# Sheet1.net
KiCad netlist of a schematic drawn in Altium Designer
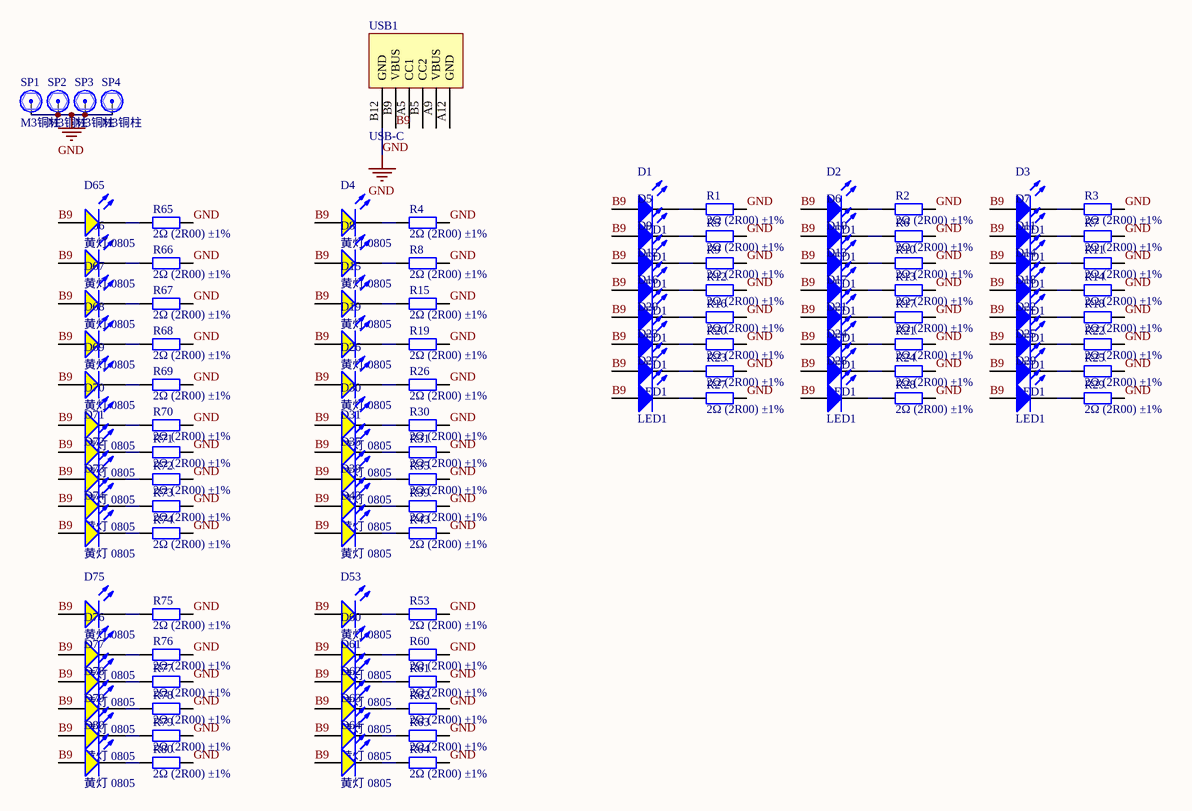
[diagram p0: Sheet1.SchDoc]

(export (version "E")
  (design (tool "Eeschema 10.0.6"))
  (components
    (comp (ref "D1")
      (value "LED1")
      (footprint "LED-1")
      (description "Typical RED GaAs LED")
      (fields (field (name "PUBLISHER") "Altium Limited"))
      (libsource (lib "Miscellaneous Devices") (part "LED1"))
    )
    (comp (ref "D2")
      (value "LED1")
      (footprint "LED-1")
      (description "Typical RED GaAs LED")
      (fields (field (name "PUBLISHER") "Altium Limited"))
      (libsource (lib "Miscellaneous Devices") (part "LED1"))
    )
    (comp (ref "D3")
      (value "LED1")
      (footprint "LED-1")
      (description "Typical RED GaAs LED")
      (fields (field (name "PUBLISHER") "Altium Limited"))
      (libsource (lib "Miscellaneous Devices") (part "LED1"))
    )
    (comp (ref "D4")
      (value "黄灯 0805")
      (footprint "0805_LED_S1")
      (description "发光二极管")
      (libsource (lib "Miscellaneous Devices LC") (part "0805 黄灯"))
    )
    (comp (ref "D5")
      (value "LED1")
      (footprint "LED-1")
      (description "Typical RED GaAs LED")
      (fields (field (name "PUBLISHER") "Altium Limited"))
      (libsource (lib "Miscellaneous Devices") (part "LED1"))
    )
    (comp (ref "D6")
      (value "LED1")
      (footprint "LED-1")
      (description "Typical RED GaAs LED")
      (fields (field (name "PUBLISHER") "Altium Limited"))
      (libsource (lib "Miscellaneous Devices") (part "LED1"))
    )
    (comp (ref "D7")
      (value "LED1")
      (footprint "LED-1")
      (description "Typical RED GaAs LED")
      (fields (field (name "PUBLISHER") "Altium Limited"))
      (libsource (lib "Miscellaneous Devices") (part "LED1"))
    )
    (comp (ref "D8")
      (value "黄灯 0805")
      (footprint "0805_LED_S1")
      (description "发光二极管")
      (libsource (lib "Miscellaneous Devices LC") (part "0805 黄灯"))
    )
    (comp (ref "D9")
      (value "LED1")
      (footprint "LED-1")
      (description "Typical RED GaAs LED")
      (fields (field (name "PUBLISHER") "Altium Limited"))
      (libsource (lib "Miscellaneous Devices") (part "LED1"))
    )
    (comp (ref "D10")
      (value "LED1")
      (footprint "LED-1")
      (description "Typical RED GaAs LED")
      (fields (field (name "PUBLISHER") "Altium Limited"))
      (libsource (lib "Miscellaneous Devices") (part "LED1"))
    )
    (comp (ref "D11")
      (value "LED1")
      (footprint "LED-1")
      (description "Typical RED GaAs LED")
      (fields (field (name "PUBLISHER") "Altium Limited"))
      (libsource (lib "Miscellaneous Devices") (part "LED1"))
    )
    (comp (ref "D12")
      (value "LED1")
      (footprint "LED-1")
      (description "Typical RED GaAs LED")
      (fields (field (name "PUBLISHER") "Altium Limited"))
      (libsource (lib "Miscellaneous Devices") (part "LED1"))
    )
    (comp (ref "D13")
      (value "LED1")
      (footprint "LED-1")
      (description "Typical RED GaAs LED")
      (fields (field (name "PUBLISHER") "Altium Limited"))
      (libsource (lib "Miscellaneous Devices") (part "LED1"))
    )
    (comp (ref "D14")
      (value "LED1")
      (footprint "LED-1")
      (description "Typical RED GaAs LED")
      (fields (field (name "PUBLISHER") "Altium Limited"))
      (libsource (lib "Miscellaneous Devices") (part "LED1"))
    )
    (comp (ref "D15")
      (value "黄灯 0805")
      (footprint "0805_LED_S1")
      (description "发光二极管")
      (libsource (lib "Miscellaneous Devices LC") (part "0805 黄灯"))
    )
    (comp (ref "D16")
      (value "LED1")
      (footprint "LED-1")
      (description "Typical RED GaAs LED")
      (fields (field (name "PUBLISHER") "Altium Limited"))
      (libsource (lib "Miscellaneous Devices") (part "LED1"))
    )
    (comp (ref "D17")
      (value "LED1")
      (footprint "LED-1")
      (description "Typical RED GaAs LED")
      (fields (field (name "PUBLISHER") "Altium Limited"))
      (libsource (lib "Miscellaneous Devices") (part "LED1"))
    )
    (comp (ref "D18")
      (value "LED1")
      (footprint "LED-1")
      (description "Typical RED GaAs LED")
      (fields (field (name "PUBLISHER") "Altium Limited"))
      (libsource (lib "Miscellaneous Devices") (part "LED1"))
    )
    (comp (ref "D19")
      (value "黄灯 0805")
      (footprint "0805_LED_S1")
      (description "发光二极管")
      (libsource (lib "Miscellaneous Devices LC") (part "0805 黄灯"))
    )
    (comp (ref "D20")
      (value "LED1")
      (footprint "LED-1")
      (description "Typical RED GaAs LED")
      (fields (field (name "PUBLISHER") "Altium Limited"))
      (libsource (lib "Miscellaneous Devices") (part "LED1"))
    )
    (comp (ref "D21")
      (value "LED1")
      (footprint "LED-1")
      (description "Typical RED GaAs LED")
      (fields (field (name "PUBLISHER") "Altium Limited"))
      (libsource (lib "Miscellaneous Devices") (part "LED1"))
    )
    (comp (ref "D22")
      (value "LED1")
      (footprint "LED-1")
      (description "Typical RED GaAs LED")
      (fields (field (name "PUBLISHER") "Altium Limited"))
      (libsource (lib "Miscellaneous Devices") (part "LED1"))
    )
    (comp (ref "D23")
      (value "LED1")
      (footprint "LED-1")
      (description "Typical RED GaAs LED")
      (fields (field (name "PUBLISHER") "Altium Limited"))
      (libsource (lib "Miscellaneous Devices") (part "LED1"))
    )
    (comp (ref "D24")
      (value "LED1")
      (footprint "LED-1")
      (description "Typical RED GaAs LED")
      (fields (field (name "PUBLISHER") "Altium Limited"))
      (libsource (lib "Miscellaneous Devices") (part "LED1"))
    )
    (comp (ref "D25")
      (value "LED1")
      (footprint "LED-1")
      (description "Typical RED GaAs LED")
      (fields (field (name "PUBLISHER") "Altium Limited"))
      (libsource (lib "Miscellaneous Devices") (part "LED1"))
    )
    (comp (ref "D26")
      (value "黄灯 0805")
      (footprint "0805_LED_S1")
      (description "发光二极管")
      (libsource (lib "Miscellaneous Devices LC") (part "0805 黄灯"))
    )
    (comp (ref "D27")
      (value "LED1")
      (footprint "LED-1")
      (description "Typical RED GaAs LED")
      (fields (field (name "PUBLISHER") "Altium Limited"))
      (libsource (lib "Miscellaneous Devices") (part "LED1"))
    )
    (comp (ref "D28")
      (value "LED1")
      (footprint "LED-1")
      (description "Typical RED GaAs LED")
      (fields (field (name "PUBLISHER") "Altium Limited"))
      (libsource (lib "Miscellaneous Devices") (part "LED1"))
    )
    (comp (ref "D29")
      (value "LED1")
      (footprint "LED-1")
      (description "Typical RED GaAs LED")
      (fields (field (name "PUBLISHER") "Altium Limited"))
      (libsource (lib "Miscellaneous Devices") (part "LED1"))
    )
    (comp (ref "D30")
      (value "黄灯 0805")
      (footprint "0805_LED_S1")
      (description "发光二极管")
      (libsource (lib "Miscellaneous Devices LC") (part "0805 黄灯"))
    )
    (comp (ref "D31")
      (value "黄灯 0805")
      (footprint "0805_LED_S1")
      (description "发光二极管")
      (libsource (lib "Miscellaneous Devices LC") (part "0805 黄灯"))
    )
    (comp (ref "D35")
      (value "黄灯 0805")
      (footprint "0805_LED_S1")
      (description "发光二极管")
      (libsource (lib "Miscellaneous Devices LC") (part "0805 黄灯"))
    )
    (comp (ref "D39")
      (value "黄灯 0805")
      (footprint "0805_LED_S1")
      (description "发光二极管")
      (libsource (lib "Miscellaneous Devices LC") (part "0805 黄灯"))
    )
    (comp (ref "D43")
      (value "黄灯 0805")
      (footprint "0805_LED_S1")
      (description "发光二极管")
      (libsource (lib "Miscellaneous Devices LC") (part "0805 黄灯"))
    )
    (comp (ref "D53")
      (value "黄灯 0805")
      (footprint "0805_LED_S1")
      (description "发光二极管")
      (libsource (lib "Miscellaneous Devices LC") (part "0805 黄灯"))
    )
    (comp (ref "D60")
      (value "黄灯 0805")
      (footprint "0805_LED_S1")
      (description "发光二极管")
      (libsource (lib "Miscellaneous Devices LC") (part "0805 黄灯"))
    )
    (comp (ref "D61")
      (value "黄灯 0805")
      (footprint "0805_LED_S1")
      (description "发光二极管")
      (libsource (lib "Miscellaneous Devices LC") (part "0805 黄灯"))
    )
    (comp (ref "D62")
      (value "黄灯 0805")
      (footprint "0805_LED_S1")
      (description "发光二极管")
      (libsource (lib "Miscellaneous Devices LC") (part "0805 黄灯"))
    )
    (comp (ref "D63")
      (value "黄灯 0805")
      (footprint "0805_LED_S1")
      (description "发光二极管")
      (libsource (lib "Miscellaneous Devices LC") (part "0805 黄灯"))
    )
    (comp (ref "D64")
      (value "黄灯 0805")
      (footprint "0805_LED_S1")
      (description "发光二极管")
      (libsource (lib "Miscellaneous Devices LC") (part "0805 黄灯"))
    )
    (comp (ref "D65")
      (value "黄灯 0805")
      (footprint "0805_LED_S1")
      (description "发光二极管")
      (libsource (lib "Miscellaneous Devices LC") (part "0805 黄灯"))
    )
    (comp (ref "D66")
      (value "黄灯 0805")
      (footprint "0805_LED_S1")
      (description "发光二极管")
      (libsource (lib "Miscellaneous Devices LC") (part "0805 黄灯"))
    )
    (comp (ref "D67")
      (value "黄灯 0805")
      (footprint "0805_LED_S1")
      (description "发光二极管")
      (libsource (lib "Miscellaneous Devices LC") (part "0805 黄灯"))
    )
    (comp (ref "D68")
      (value "黄灯 0805")
      (footprint "0805_LED_S1")
      (description "发光二极管")
      (libsource (lib "Miscellaneous Devices LC") (part "0805 黄灯"))
    )
    (comp (ref "D69")
      (value "黄灯 0805")
      (footprint "0805_LED_S1")
      (description "发光二极管")
      (libsource (lib "Miscellaneous Devices LC") (part "0805 黄灯"))
    )
    (comp (ref "D70")
      (value "黄灯 0805")
      (footprint "0805_LED_S1")
      (description "发光二极管")
      (libsource (lib "Miscellaneous Devices LC") (part "0805 黄灯"))
    )
    (comp (ref "D71")
      (value "黄灯 0805")
      (footprint "0805_LED_S1")
      (description "发光二极管")
      (libsource (lib "Miscellaneous Devices LC") (part "0805 黄灯"))
    )
    (comp (ref "D72")
      (value "黄灯 0805")
      (footprint "0805_LED_S1")
      (description "发光二极管")
      (libsource (lib "Miscellaneous Devices LC") (part "0805 黄灯"))
    )
    (comp (ref "D73")
      (value "黄灯 0805")
      (footprint "0805_LED_S1")
      (description "发光二极管")
      (libsource (lib "Miscellaneous Devices LC") (part "0805 黄灯"))
    )
    (comp (ref "D74")
      (value "黄灯 0805")
      (footprint "0805_LED_S1")
      (description "发光二极管")
      (libsource (lib "Miscellaneous Devices LC") (part "0805 黄灯"))
    )
    (comp (ref "D75")
      (value "黄灯 0805")
      (footprint "0805_LED_S1")
      (description "发光二极管")
      (libsource (lib "Miscellaneous Devices LC") (part "0805 黄灯"))
    )
    (comp (ref "D76")
      (value "黄灯 0805")
      (footprint "0805_LED_S1")
      (description "发光二极管")
      (libsource (lib "Miscellaneous Devices LC") (part "0805 黄灯"))
    )
    (comp (ref "D77")
      (value "黄灯 0805")
      (footprint "0805_LED_S1")
      (description "发光二极管")
      (libsource (lib "Miscellaneous Devices LC") (part "0805 黄灯"))
    )
    (comp (ref "D78")
      (value "黄灯 0805")
      (footprint "0805_LED_S1")
      (description "发光二极管")
      (libsource (lib "Miscellaneous Devices LC") (part "0805 黄灯"))
    )
    (comp (ref "D79")
      (value "黄灯 0805")
      (footprint "0805_LED_S1")
      (description "发光二极管")
      (libsource (lib "Miscellaneous Devices LC") (part "0805 黄灯"))
    )
    (comp (ref "D80")
      (value "黄灯 0805")
      (footprint "0805_LED_S1")
      (description "发光二极管")
      (libsource (lib "Miscellaneous Devices LC") (part "0805 黄灯"))
    )
    (comp (ref "R1")
      (value "2Ω (2R00) ±1%")
      (footprint "0805_R")
      (description "贴片电阻")
      (libsource (lib "Miscellaneous Devices LC") (part "0805 2Ω (2R00) 1%"))
    )
    (comp (ref "R2")
      (value "2Ω (2R00) ±1%")
      (footprint "0805_R")
      (description "贴片电阻")
      (libsource (lib "Miscellaneous Devices LC") (part "0805 2Ω (2R00) 1%"))
    )
    (comp (ref "R3")
      (value "2Ω (2R00) ±1%")
      (footprint "0805_R")
      (description "贴片电阻")
      (libsource (lib "Miscellaneous Devices LC") (part "0805 2Ω (2R00) 1%"))
    )
    (comp (ref "R4")
      (value "2Ω (2R00) ±1%")
      (footprint "0805_R")
      (description "贴片电阻")
      (libsource (lib "Miscellaneous Devices LC") (part "0805 2Ω (2R00) 1%"))
    )
    (comp (ref "R5")
      (value "2Ω (2R00) ±1%")
      (footprint "0805_R")
      (description "贴片电阻")
      (libsource (lib "Miscellaneous Devices LC") (part "0805 2Ω (2R00) 1%"))
    )
    (comp (ref "R6")
      (value "2Ω (2R00) ±1%")
      (footprint "0805_R")
      (description "贴片电阻")
      (libsource (lib "Miscellaneous Devices LC") (part "0805 2Ω (2R00) 1%"))
    )
    (comp (ref "R7")
      (value "2Ω (2R00) ±1%")
      (footprint "0805_R")
      (description "贴片电阻")
      (libsource (lib "Miscellaneous Devices LC") (part "0805 2Ω (2R00) 1%"))
    )
    (comp (ref "R8")
      (value "2Ω (2R00) ±1%")
      (footprint "0805_R")
      (description "贴片电阻")
      (libsource (lib "Miscellaneous Devices LC") (part "0805 2Ω (2R00) 1%"))
    )
    (comp (ref "R9")
      (value "2Ω (2R00) ±1%")
      (footprint "0805_R")
      (description "贴片电阻")
      (libsource (lib "Miscellaneous Devices LC") (part "0805 2Ω (2R00) 1%"))
    )
    (comp (ref "R10")
      (value "2Ω (2R00) ±1%")
      (footprint "0805_R")
      (description "贴片电阻")
      (libsource (lib "Miscellaneous Devices LC") (part "0805 2Ω (2R00) 1%"))
    )
    (comp (ref "R11")
      (value "2Ω (2R00) ±1%")
      (footprint "0805_R")
      (description "贴片电阻")
      (libsource (lib "Miscellaneous Devices LC") (part "0805 2Ω (2R00) 1%"))
    )
    (comp (ref "R12")
      (value "2Ω (2R00) ±1%")
      (footprint "0805_R")
      (description "贴片电阻")
      (libsource (lib "Miscellaneous Devices LC") (part "0805 2Ω (2R00) 1%"))
    )
    (comp (ref "R13")
      (value "2Ω (2R00) ±1%")
      (footprint "0805_R")
      (description "贴片电阻")
      (libsource (lib "Miscellaneous Devices LC") (part "0805 2Ω (2R00) 1%"))
    )
    (comp (ref "R14")
      (value "2Ω (2R00) ±1%")
      (footprint "0805_R")
      (description "贴片电阻")
      (libsource (lib "Miscellaneous Devices LC") (part "0805 2Ω (2R00) 1%"))
    )
    (comp (ref "R15")
      (value "2Ω (2R00) ±1%")
      (footprint "0805_R")
      (description "贴片电阻")
      (libsource (lib "Miscellaneous Devices LC") (part "0805 2Ω (2R00) 1%"))
    )
    (comp (ref "R16")
      (value "2Ω (2R00) ±1%")
      (footprint "0805_R")
      (description "贴片电阻")
      (libsource (lib "Miscellaneous Devices LC") (part "0805 2Ω (2R00) 1%"))
    )
    (comp (ref "R17")
      (value "2Ω (2R00) ±1%")
      (footprint "0805_R")
      (description "贴片电阻")
      (libsource (lib "Miscellaneous Devices LC") (part "0805 2Ω (2R00) 1%"))
    )
    (comp (ref "R18")
      (value "2Ω (2R00) ±1%")
      (footprint "0805_R")
      (description "贴片电阻")
      (libsource (lib "Miscellaneous Devices LC") (part "0805 2Ω (2R00) 1%"))
    )
    (comp (ref "R19")
      (value "2Ω (2R00) ±1%")
      (footprint "0805_R")
      (description "贴片电阻")
      (libsource (lib "Miscellaneous Devices LC") (part "0805 2Ω (2R00) 1%"))
    )
    (comp (ref "R20")
      (value "2Ω (2R00) ±1%")
      (footprint "0805_R")
      (description "贴片电阻")
      (libsource (lib "Miscellaneous Devices LC") (part "0805 2Ω (2R00) 1%"))
    )
    (comp (ref "R21")
      (value "2Ω (2R00) ±1%")
      (footprint "0805_R")
      (description "贴片电阻")
      (libsource (lib "Miscellaneous Devices LC") (part "0805 2Ω (2R00) 1%"))
    )
    (comp (ref "R22")
      (value "2Ω (2R00) ±1%")
      (footprint "0805_R")
      (description "贴片电阻")
      (libsource (lib "Miscellaneous Devices LC") (part "0805 2Ω (2R00) 1%"))
    )
    (comp (ref "R23")
      (value "2Ω (2R00) ±1%")
      (footprint "0805_R")
      (description "贴片电阻")
      (libsource (lib "Miscellaneous Devices LC") (part "0805 2Ω (2R00) 1%"))
    )
    (comp (ref "R24")
      (value "2Ω (2R00) ±1%")
      (footprint "0805_R")
      (description "贴片电阻")
      (libsource (lib "Miscellaneous Devices LC") (part "0805 2Ω (2R00) 1%"))
    )
    (comp (ref "R25")
      (value "2Ω (2R00) ±1%")
      (footprint "0805_R")
      (description "贴片电阻")
      (libsource (lib "Miscellaneous Devices LC") (part "0805 2Ω (2R00) 1%"))
    )
    (comp (ref "R26")
      (value "2Ω (2R00) ±1%")
      (footprint "0805_R")
      (description "贴片电阻")
      (libsource (lib "Miscellaneous Devices LC") (part "0805 2Ω (2R00) 1%"))
    )
    (comp (ref "R27")
      (value "2Ω (2R00) ±1%")
      (footprint "0805_R")
      (description "贴片电阻")
      (libsource (lib "Miscellaneous Devices LC") (part "0805 2Ω (2R00) 1%"))
    )
    (comp (ref "R28")
      (value "2Ω (2R00) ±1%")
      (footprint "0805_R")
      (description "贴片电阻")
      (libsource (lib "Miscellaneous Devices LC") (part "0805 2Ω (2R00) 1%"))
    )
    (comp (ref "R29")
      (value "2Ω (2R00) ±1%")
      (footprint "0805_R")
      (description "贴片电阻")
      (libsource (lib "Miscellaneous Devices LC") (part "0805 2Ω (2R00) 1%"))
    )
    (comp (ref "R30")
      (value "2Ω (2R00) ±1%")
      (footprint "0805_R")
      (description "贴片电阻")
      (libsource (lib "Miscellaneous Devices LC") (part "0805 2Ω (2R00) 1%"))
    )
    (comp (ref "R31")
      (value "2Ω (2R00) ±1%")
      (footprint "0805_R")
      (description "贴片电阻")
      (libsource (lib "Miscellaneous Devices LC") (part "0805 2Ω (2R00) 1%"))
    )
    (comp (ref "R35")
      (value "2Ω (2R00) ±1%")
      (footprint "0805_R")
      (description "贴片电阻")
      (libsource (lib "Miscellaneous Devices LC") (part "0805 2Ω (2R00) 1%"))
    )
    (comp (ref "R39")
      (value "2Ω (2R00) ±1%")
      (footprint "0805_R")
      (description "贴片电阻")
      (libsource (lib "Miscellaneous Devices LC") (part "0805 2Ω (2R00) 1%"))
    )
    (comp (ref "R43")
      (value "2Ω (2R00) ±1%")
      (footprint "0805_R")
      (description "贴片电阻")
      (libsource (lib "Miscellaneous Devices LC") (part "0805 2Ω (2R00) 1%"))
    )
    (comp (ref "R53")
      (value "2Ω (2R00) ±1%")
      (footprint "0805_R")
      (description "贴片电阻")
      (libsource (lib "Miscellaneous Devices LC") (part "0805 2Ω (2R00) 1%"))
    )
    (comp (ref "R60")
      (value "2Ω (2R00) ±1%")
      (footprint "0805_R")
      (description "贴片电阻")
      (libsource (lib "Miscellaneous Devices LC") (part "0805 2Ω (2R00) 1%"))
    )
    (comp (ref "R61")
      (value "2Ω (2R00) ±1%")
      (footprint "0805_R")
      (description "贴片电阻")
      (libsource (lib "Miscellaneous Devices LC") (part "0805 2Ω (2R00) 1%"))
    )
    (comp (ref "R62")
      (value "2Ω (2R00) ±1%")
      (footprint "0805_R")
      (description "贴片电阻")
      (libsource (lib "Miscellaneous Devices LC") (part "0805 2Ω (2R00) 1%"))
    )
    (comp (ref "R63")
      (value "2Ω (2R00) ±1%")
      (footprint "0805_R")
      (description "贴片电阻")
      (libsource (lib "Miscellaneous Devices LC") (part "0805 2Ω (2R00) 1%"))
    )
    (comp (ref "R64")
      (value "2Ω (2R00) ±1%")
      (footprint "0805_R")
      (description "贴片电阻")
      (libsource (lib "Miscellaneous Devices LC") (part "0805 2Ω (2R00) 1%"))
    )
    (comp (ref "R65")
      (value "2Ω (2R00) ±1%")
      (footprint "0805_R")
      (description "贴片电阻")
      (libsource (lib "Miscellaneous Devices LC") (part "0805 2Ω (2R00) 1%"))
    )
    (comp (ref "R66")
      (value "2Ω (2R00) ±1%")
      (footprint "0805_R")
      (description "贴片电阻")
      (libsource (lib "Miscellaneous Devices LC") (part "0805 2Ω (2R00) 1%"))
    )
    (comp (ref "R67")
      (value "2Ω (2R00) ±1%")
      (footprint "0805_R")
      (description "贴片电阻")
      (libsource (lib "Miscellaneous Devices LC") (part "0805 2Ω (2R00) 1%"))
    )
    (comp (ref "R68")
      (value "2Ω (2R00) ±1%")
      (footprint "0805_R")
      (description "贴片电阻")
      (libsource (lib "Miscellaneous Devices LC") (part "0805 2Ω (2R00) 1%"))
    )
    (comp (ref "R69")
      (value "2Ω (2R00) ±1%")
      (footprint "0805_R")
      (description "贴片电阻")
      (libsource (lib "Miscellaneous Devices LC") (part "0805 2Ω (2R00) 1%"))
    )
    (comp (ref "R70")
      (value "2Ω (2R00) ±1%")
      (footprint "0805_R")
      (description "贴片电阻")
      (libsource (lib "Miscellaneous Devices LC") (part "0805 2Ω (2R00) 1%"))
    )
    (comp (ref "R71")
      (value "2Ω (2R00) ±1%")
      (footprint "0805_R")
      (description "贴片电阻")
      (libsource (lib "Miscellaneous Devices LC") (part "0805 2Ω (2R00) 1%"))
    )
    (comp (ref "R72")
      (value "2Ω (2R00) ±1%")
      (footprint "0805_R")
      (description "贴片电阻")
      (libsource (lib "Miscellaneous Devices LC") (part "0805 2Ω (2R00) 1%"))
    )
    (comp (ref "R73")
      (value "2Ω (2R00) ±1%")
      (footprint "0805_R")
      (description "贴片电阻")
      (libsource (lib "Miscellaneous Devices LC") (part "0805 2Ω (2R00) 1%"))
    )
    (comp (ref "R74")
      (value "2Ω (2R00) ±1%")
      (footprint "0805_R")
      (description "贴片电阻")
      (libsource (lib "Miscellaneous Devices LC") (part "0805 2Ω (2R00) 1%"))
    )
    (comp (ref "R75")
      (value "2Ω (2R00) ±1%")
      (footprint "0805_R")
      (description "贴片电阻")
      (libsource (lib "Miscellaneous Devices LC") (part "0805 2Ω (2R00) 1%"))
    )
    (comp (ref "R76")
      (value "2Ω (2R00) ±1%")
      (footprint "0805_R")
      (description "贴片电阻")
      (libsource (lib "Miscellaneous Devices LC") (part "0805 2Ω (2R00) 1%"))
    )
    (comp (ref "R77")
      (value "2Ω (2R00) ±1%")
      (footprint "0805_R")
      (description "贴片电阻")
      (libsource (lib "Miscellaneous Devices LC") (part "0805 2Ω (2R00) 1%"))
    )
    (comp (ref "R78")
      (value "2Ω (2R00) ±1%")
      (footprint "0805_R")
      (description "贴片电阻")
      (libsource (lib "Miscellaneous Devices LC") (part "0805 2Ω (2R00) 1%"))
    )
    (comp (ref "R79")
      (value "2Ω (2R00) ±1%")
      (footprint "0805_R")
      (description "贴片电阻")
      (libsource (lib "Miscellaneous Devices LC") (part "0805 2Ω (2R00) 1%"))
    )
    (comp (ref "R80")
      (value "2Ω (2R00) ±1%")
      (footprint "0805_R")
      (description "贴片电阻")
      (libsource (lib "Miscellaneous Devices LC") (part "0805 2Ω (2R00) 1%"))
    )
    (comp (ref "SP1")
      (value "M3铜柱")
      (footprint "M3x4_L")
      (description "铜柱")
      (libsource (lib "铜柱-测试点-电池座-蜂鸣器") (part "铜柱小焊盘"))
    )
    (comp (ref "SP2")
      (value "M3铜柱")
      (footprint "M3x4_L")
      (description "铜柱")
      (libsource (lib "铜柱-测试点-电池座-蜂鸣器") (part "铜柱小焊盘"))
    )
    (comp (ref "SP3")
      (value "M3铜柱")
      (footprint "M3x4_L")
      (description "铜柱")
      (libsource (lib "铜柱-测试点-电池座-蜂鸣器") (part "铜柱小焊盘"))
    )
    (comp (ref "SP4")
      (value "M3铜柱")
      (footprint "M3x4_L")
      (description "铜柱")
      (libsource (lib "铜柱-测试点-电池座-蜂鸣器") (part "铜柱小焊盘"))
    )
    (comp (ref "USB1")
      (value "USB-C")
      (footprint "USB-C/S_C")
      (description "USB-C_6P型母接口")
      (libsource (lib "接口") (part "USB-C_6P/S"))
    )
  )
  (nets
    (net (code "1") (name "/B9") (class "Default")
      (node (ref "D1") (pin "1") (pinfunction "A_1") (pintype "passive"))
      (node (ref "D10") (pin "1") (pinfunction "A_1") (pintype "passive"))
      (node (ref "D11") (pin "1") (pinfunction "A_1") (pintype "passive"))
      (node (ref "D12") (pin "1") (pinfunction "A_1") (pintype "passive"))
      (node (ref "D13") (pin "1") (pinfunction "A_1") (pintype "passive"))
      (node (ref "D14") (pin "1") (pinfunction "A_1") (pintype "passive"))
      (node (ref "D15") (pin "A") (pinfunction "A_A") (pintype "passive"))
      (node (ref "D16") (pin "1") (pinfunction "A_1") (pintype "passive"))
      (node (ref "D17") (pin "1") (pinfunction "A_1") (pintype "passive"))
      (node (ref "D18") (pin "1") (pinfunction "A_1") (pintype "passive"))
      (node (ref "D19") (pin "A") (pinfunction "A_A") (pintype "passive"))
      (node (ref "D2") (pin "1") (pinfunction "A_1") (pintype "passive"))
      (node (ref "D20") (pin "1") (pinfunction "A_1") (pintype "passive"))
      (node (ref "D21") (pin "1") (pinfunction "A_1") (pintype "passive"))
      (node (ref "D22") (pin "1") (pinfunction "A_1") (pintype "passive"))
      (node (ref "D23") (pin "1") (pinfunction "A_1") (pintype "passive"))
      (node (ref "D24") (pin "1") (pinfunction "A_1") (pintype "passive"))
      (node (ref "D25") (pin "1") (pinfunction "A_1") (pintype "passive"))
      (node (ref "D26") (pin "A") (pinfunction "A_A") (pintype "passive"))
      (node (ref "D27") (pin "1") (pinfunction "A_1") (pintype "passive"))
      (node (ref "D28") (pin "1") (pinfunction "A_1") (pintype "passive"))
      (node (ref "D29") (pin "1") (pinfunction "A_1") (pintype "passive"))
      (node (ref "D3") (pin "1") (pinfunction "A_1") (pintype "passive"))
      (node (ref "D30") (pin "A") (pinfunction "A_A") (pintype "passive"))
      (node (ref "D31") (pin "A") (pinfunction "A_A") (pintype "passive"))
      (node (ref "D35") (pin "A") (pinfunction "A_A") (pintype "passive"))
      (node (ref "D39") (pin "A") (pinfunction "A_A") (pintype "passive"))
      (node (ref "D4") (pin "A") (pinfunction "A_A") (pintype "passive"))
      (node (ref "D43") (pin "A") (pinfunction "A_A") (pintype "passive"))
      (node (ref "D5") (pin "1") (pinfunction "A_1") (pintype "passive"))
      (node (ref "D53") (pin "A") (pinfunction "A_A") (pintype "passive"))
      (node (ref "D6") (pin "1") (pinfunction "A_1") (pintype "passive"))
      (node (ref "D60") (pin "A") (pinfunction "A_A") (pintype "passive"))
      (node (ref "D61") (pin "A") (pinfunction "A_A") (pintype "passive"))
      (node (ref "D62") (pin "A") (pinfunction "A_A") (pintype "passive"))
      (node (ref "D63") (pin "A") (pinfunction "A_A") (pintype "passive"))
      (node (ref "D64") (pin "A") (pinfunction "A_A") (pintype "passive"))
      (node (ref "D65") (pin "A") (pinfunction "A_A") (pintype "passive"))
      (node (ref "D66") (pin "A") (pinfunction "A_A") (pintype "passive"))
      (node (ref "D67") (pin "A") (pinfunction "A_A") (pintype "passive"))
      (node (ref "D68") (pin "A") (pinfunction "A_A") (pintype "passive"))
      (node (ref "D69") (pin "A") (pinfunction "A_A") (pintype "passive"))
      (node (ref "D7") (pin "1") (pinfunction "A_1") (pintype "passive"))
      (node (ref "D70") (pin "A") (pinfunction "A_A") (pintype "passive"))
      (node (ref "D71") (pin "A") (pinfunction "A_A") (pintype "passive"))
      (node (ref "D72") (pin "A") (pinfunction "A_A") (pintype "passive"))
      (node (ref "D73") (pin "A") (pinfunction "A_A") (pintype "passive"))
      (node (ref "D74") (pin "A") (pinfunction "A_A") (pintype "passive"))
      (node (ref "D75") (pin "A") (pinfunction "A_A") (pintype "passive"))
      (node (ref "D76") (pin "A") (pinfunction "A_A") (pintype "passive"))
      (node (ref "D77") (pin "A") (pinfunction "A_A") (pintype "passive"))
      (node (ref "D78") (pin "A") (pinfunction "A_A") (pintype "passive"))
      (node (ref "D79") (pin "A") (pinfunction "A_A") (pintype "passive"))
      (node (ref "D8") (pin "A") (pinfunction "A_A") (pintype "passive"))
      (node (ref "D80") (pin "A") (pinfunction "A_A") (pintype "passive"))
      (node (ref "D9") (pin "1") (pinfunction "A_1") (pintype "passive"))
      (node (ref "USB1") (pin "B9") (pinfunction "VBUS_B9") (pintype "passive"))
    )
    (net (code "2") (name "GND") (class "Default")
      (node (ref "R1") (pin "2") (pinfunction "2_2") (pintype "passive"))
      (node (ref "R10") (pin "2") (pinfunction "2_2") (pintype "passive"))
      (node (ref "R11") (pin "2") (pinfunction "2_2") (pintype "passive"))
      (node (ref "R12") (pin "2") (pinfunction "2_2") (pintype "passive"))
      (node (ref "R13") (pin "2") (pinfunction "2_2") (pintype "passive"))
      (node (ref "R14") (pin "2") (pinfunction "2_2") (pintype "passive"))
      (node (ref "R15") (pin "2") (pinfunction "2_2") (pintype "passive"))
      (node (ref "R16") (pin "2") (pinfunction "2_2") (pintype "passive"))
      (node (ref "R17") (pin "2") (pinfunction "2_2") (pintype "passive"))
      (node (ref "R18") (pin "2") (pinfunction "2_2") (pintype "passive"))
      (node (ref "R19") (pin "2") (pinfunction "2_2") (pintype "passive"))
      (node (ref "R2") (pin "2") (pinfunction "2_2") (pintype "passive"))
      (node (ref "R20") (pin "2") (pinfunction "2_2") (pintype "passive"))
      (node (ref "R21") (pin "2") (pinfunction "2_2") (pintype "passive"))
      (node (ref "R22") (pin "2") (pinfunction "2_2") (pintype "passive"))
      (node (ref "R23") (pin "2") (pinfunction "2_2") (pintype "passive"))
      (node (ref "R24") (pin "2") (pinfunction "2_2") (pintype "passive"))
      (node (ref "R25") (pin "2") (pinfunction "2_2") (pintype "passive"))
      (node (ref "R26") (pin "2") (pinfunction "2_2") (pintype "passive"))
      (node (ref "R27") (pin "2") (pinfunction "2_2") (pintype "passive"))
      (node (ref "R28") (pin "2") (pinfunction "2_2") (pintype "passive"))
      (node (ref "R29") (pin "2") (pinfunction "2_2") (pintype "passive"))
      (node (ref "R3") (pin "2") (pinfunction "2_2") (pintype "passive"))
      (node (ref "R30") (pin "2") (pinfunction "2_2") (pintype "passive"))
      (node (ref "R31") (pin "2") (pinfunction "2_2") (pintype "passive"))
      (node (ref "R35") (pin "2") (pinfunction "2_2") (pintype "passive"))
      (node (ref "R39") (pin "2") (pinfunction "2_2") (pintype "passive"))
      (node (ref "R4") (pin "2") (pinfunction "2_2") (pintype "passive"))
      (node (ref "R43") (pin "2") (pinfunction "2_2") (pintype "passive"))
      (node (ref "R5") (pin "2") (pinfunction "2_2") (pintype "passive"))
      (node (ref "R53") (pin "2") (pinfunction "2_2") (pintype "passive"))
      (node (ref "R6") (pin "2") (pinfunction "2_2") (pintype "passive"))
      (node (ref "R60") (pin "2") (pinfunction "2_2") (pintype "passive"))
      (node (ref "R61") (pin "2") (pinfunction "2_2") (pintype "passive"))
      (node (ref "R62") (pin "2") (pinfunction "2_2") (pintype "passive"))
      (node (ref "R63") (pin "2") (pinfunction "2_2") (pintype "passive"))
      (node (ref "R64") (pin "2") (pinfunction "2_2") (pintype "passive"))
      (node (ref "R65") (pin "2") (pinfunction "2_2") (pintype "passive"))
      (node (ref "R66") (pin "2") (pinfunction "2_2") (pintype "passive"))
      (node (ref "R67") (pin "2") (pinfunction "2_2") (pintype "passive"))
      (node (ref "R68") (pin "2") (pinfunction "2_2") (pintype "passive"))
      (node (ref "R69") (pin "2") (pinfunction "2_2") (pintype "passive"))
      (node (ref "R7") (pin "2") (pinfunction "2_2") (pintype "passive"))
      (node (ref "R70") (pin "2") (pinfunction "2_2") (pintype "passive"))
      (node (ref "R71") (pin "2") (pinfunction "2_2") (pintype "passive"))
      (node (ref "R72") (pin "2") (pinfunction "2_2") (pintype "passive"))
      (node (ref "R73") (pin "2") (pinfunction "2_2") (pintype "passive"))
      (node (ref "R74") (pin "2") (pinfunction "2_2") (pintype "passive"))
      (node (ref "R75") (pin "2") (pinfunction "2_2") (pintype "passive"))
      (node (ref "R76") (pin "2") (pinfunction "2_2") (pintype "passive"))
      (node (ref "R77") (pin "2") (pinfunction "2_2") (pintype "passive"))
      (node (ref "R78") (pin "2") (pinfunction "2_2") (pintype "passive"))
      (node (ref "R79") (pin "2") (pinfunction "2_2") (pintype "passive"))
      (node (ref "R8") (pin "2") (pinfunction "2_2") (pintype "passive"))
      (node (ref "R80") (pin "2") (pinfunction "2_2") (pintype "passive"))
      (node (ref "R9") (pin "2") (pinfunction "2_2") (pintype "passive"))
      (node (ref "SP1") (pin "1") (pinfunction "1_1") (pintype "passive"))
      (node (ref "SP2") (pin "1") (pinfunction "1_1") (pintype "passive"))
      (node (ref "SP3") (pin "1") (pinfunction "1_1") (pintype "passive"))
      (node (ref "SP4") (pin "1") (pinfunction "1_1") (pintype "passive"))
      (node (ref "USB1") (pin "B12") (pinfunction "GND_B12") (pintype "passive"))
    )
    (net (code "3") (name "Net-(D1-K)") (class "Default")
      (node (ref "D1") (pin "2") (pinfunction "K_2") (pintype "passive"))
      (node (ref "R1") (pin "1") (pinfunction "1_1") (pintype "passive"))
    )
    (net (code "4") (name "Net-(D2-K)") (class "Default")
      (node (ref "D2") (pin "2") (pinfunction "K_2") (pintype "passive"))
      (node (ref "R2") (pin "1") (pinfunction "1_1") (pintype "passive"))
    )
    (net (code "5") (name "Net-(D3-K)") (class "Default")
      (node (ref "D3") (pin "2") (pinfunction "K_2") (pintype "passive"))
      (node (ref "R3") (pin "1") (pinfunction "1_1") (pintype "passive"))
    )
    (net (code "6") (name "Net-(D4-PadK)") (class "Default")
      (node (ref "D4") (pin "K") (pinfunction "K_K") (pintype "passive"))
      (node (ref "R4") (pin "1") (pinfunction "1_1") (pintype "passive"))
    )
    (net (code "7") (name "Net-(D5-K)") (class "Default")
      (node (ref "D5") (pin "2") (pinfunction "K_2") (pintype "passive"))
      (node (ref "R5") (pin "1") (pinfunction "1_1") (pintype "passive"))
    )
    (net (code "8") (name "Net-(D6-K)") (class "Default")
      (node (ref "D6") (pin "2") (pinfunction "K_2") (pintype "passive"))
      (node (ref "R6") (pin "1") (pinfunction "1_1") (pintype "passive"))
    )
    (net (code "9") (name "Net-(D7-K)") (class "Default")
      (node (ref "D7") (pin "2") (pinfunction "K_2") (pintype "passive"))
      (node (ref "R7") (pin "1") (pinfunction "1_1") (pintype "passive"))
    )
    (net (code "10") (name "Net-(D8-PadK)") (class "Default")
      (node (ref "D8") (pin "K") (pinfunction "K_K") (pintype "passive"))
      (node (ref "R8") (pin "1") (pinfunction "1_1") (pintype "passive"))
    )
    (net (code "11") (name "Net-(D9-K)") (class "Default")
      (node (ref "D9") (pin "2") (pinfunction "K_2") (pintype "passive"))
      (node (ref "R9") (pin "1") (pinfunction "1_1") (pintype "passive"))
    )
    (net (code "12") (name "Net-(D10-K)") (class "Default")
      (node (ref "D10") (pin "2") (pinfunction "K_2") (pintype "passive"))
      (node (ref "R10") (pin "1") (pinfunction "1_1") (pintype "passive"))
    )
    (net (code "13") (name "Net-(D11-K)") (class "Default")
      (node (ref "D11") (pin "2") (pinfunction "K_2") (pintype "passive"))
      (node (ref "R11") (pin "1") (pinfunction "1_1") (pintype "passive"))
    )
    (net (code "14") (name "Net-(D12-K)") (class "Default")
      (node (ref "D12") (pin "2") (pinfunction "K_2") (pintype "passive"))
      (node (ref "R12") (pin "1") (pinfunction "1_1") (pintype "passive"))
    )
    (net (code "15") (name "Net-(D13-K)") (class "Default")
      (node (ref "D13") (pin "2") (pinfunction "K_2") (pintype "passive"))
      (node (ref "R13") (pin "1") (pinfunction "1_1") (pintype "passive"))
    )
    (net (code "16") (name "Net-(D14-K)") (class "Default")
      (node (ref "D14") (pin "2") (pinfunction "K_2") (pintype "passive"))
      (node (ref "R14") (pin "1") (pinfunction "1_1") (pintype "passive"))
    )
    (net (code "17") (name "Net-(D15-PadK)") (class "Default")
      (node (ref "D15") (pin "K") (pinfunction "K_K") (pintype "passive"))
      (node (ref "R15") (pin "1") (pinfunction "1_1") (pintype "passive"))
    )
    (net (code "18") (name "Net-(D16-K)") (class "Default")
      (node (ref "D16") (pin "2") (pinfunction "K_2") (pintype "passive"))
      (node (ref "R16") (pin "1") (pinfunction "1_1") (pintype "passive"))
    )
    (net (code "19") (name "Net-(D17-K)") (class "Default")
      (node (ref "D17") (pin "2") (pinfunction "K_2") (pintype "passive"))
      (node (ref "R17") (pin "1") (pinfunction "1_1") (pintype "passive"))
    )
    (net (code "20") (name "Net-(D18-K)") (class "Default")
      (node (ref "D18") (pin "2") (pinfunction "K_2") (pintype "passive"))
      (node (ref "R18") (pin "1") (pinfunction "1_1") (pintype "passive"))
    )
    (net (code "21") (name "Net-(D19-PadK)") (class "Default")
      (node (ref "D19") (pin "K") (pinfunction "K_K") (pintype "passive"))
      (node (ref "R19") (pin "1") (pinfunction "1_1") (pintype "passive"))
    )
    (net (code "22") (name "Net-(D20-K)") (class "Default")
      (node (ref "D20") (pin "2") (pinfunction "K_2") (pintype "passive"))
      (node (ref "R20") (pin "1") (pinfunction "1_1") (pintype "passive"))
    )
    (net (code "23") (name "Net-(D21-K)") (class "Default")
      (node (ref "D21") (pin "2") (pinfunction "K_2") (pintype "passive"))
      (node (ref "R21") (pin "1") (pinfunction "1_1") (pintype "passive"))
    )
    (net (code "24") (name "Net-(D22-K)") (class "Default")
      (node (ref "D22") (pin "2") (pinfunction "K_2") (pintype "passive"))
      (node (ref "R22") (pin "1") (pinfunction "1_1") (pintype "passive"))
    )
    (net (code "25") (name "Net-(D23-K)") (class "Default")
      (node (ref "D23") (pin "2") (pinfunction "K_2") (pintype "passive"))
      (node (ref "R23") (pin "1") (pinfunction "1_1") (pintype "passive"))
    )
    (net (code "26") (name "Net-(D24-K)") (class "Default")
      (node (ref "D24") (pin "2") (pinfunction "K_2") (pintype "passive"))
      (node (ref "R24") (pin "1") (pinfunction "1_1") (pintype "passive"))
    )
    (net (code "27") (name "Net-(D25-K)") (class "Default")
      (node (ref "D25") (pin "2") (pinfunction "K_2") (pintype "passive"))
      (node (ref "R25") (pin "1") (pinfunction "1_1") (pintype "passive"))
    )
    (net (code "28") (name "Net-(D26-PadK)") (class "Default")
      (node (ref "D26") (pin "K") (pinfunction "K_K") (pintype "passive"))
      (node (ref "R26") (pin "1") (pinfunction "1_1") (pintype "passive"))
    )
    (net (code "29") (name "Net-(D27-K)") (class "Default")
      (node (ref "D27") (pin "2") (pinfunction "K_2") (pintype "passive"))
      (node (ref "R27") (pin "1") (pinfunction "1_1") (pintype "passive"))
    )
    (net (code "30") (name "Net-(D28-K)") (class "Default")
      (node (ref "D28") (pin "2") (pinfunction "K_2") (pintype "passive"))
      (node (ref "R28") (pin "1") (pinfunction "1_1") (pintype "passive"))
    )
    (net (code "31") (name "Net-(D29-K)") (class "Default")
      (node (ref "D29") (pin "2") (pinfunction "K_2") (pintype "passive"))
      (node (ref "R29") (pin "1") (pinfunction "1_1") (pintype "passive"))
    )
    (net (code "32") (name "Net-(D30-PadK)") (class "Default")
      (node (ref "D30") (pin "K") (pinfunction "K_K") (pintype "passive"))
      (node (ref "R30") (pin "1") (pinfunction "1_1") (pintype "passive"))
    )
    (net (code "33") (name "Net-(D31-PadK)") (class "Default")
      (node (ref "D31") (pin "K") (pinfunction "K_K") (pintype "passive"))
      (node (ref "R31") (pin "1") (pinfunction "1_1") (pintype "passive"))
    )
    (net (code "34") (name "Net-(D35-PadK)") (class "Default")
      (node (ref "D35") (pin "K") (pinfunction "K_K") (pintype "passive"))
      (node (ref "R35") (pin "1") (pinfunction "1_1") (pintype "passive"))
    )
    (net (code "35") (name "Net-(D39-PadK)") (class "Default")
      (node (ref "D39") (pin "K") (pinfunction "K_K") (pintype "passive"))
      (node (ref "R39") (pin "1") (pinfunction "1_1") (pintype "passive"))
    )
    (net (code "36") (name "Net-(D43-PadK)") (class "Default")
      (node (ref "D43") (pin "K") (pinfunction "K_K") (pintype "passive"))
      (node (ref "R43") (pin "1") (pinfunction "1_1") (pintype "passive"))
    )
    (net (code "37") (name "Net-(D53-PadK)") (class "Default")
      (node (ref "D53") (pin "K") (pinfunction "K_K") (pintype "passive"))
      (node (ref "R53") (pin "1") (pinfunction "1_1") (pintype "passive"))
    )
    (net (code "38") (name "Net-(D60-PadK)") (class "Default")
      (node (ref "D60") (pin "K") (pinfunction "K_K") (pintype "passive"))
      (node (ref "R60") (pin "1") (pinfunction "1_1") (pintype "passive"))
    )
    (net (code "39") (name "Net-(D61-PadK)") (class "Default")
      (node (ref "D61") (pin "K") (pinfunction "K_K") (pintype "passive"))
      (node (ref "R61") (pin "1") (pinfunction "1_1") (pintype "passive"))
    )
    (net (code "40") (name "Net-(D62-PadK)") (class "Default")
      (node (ref "D62") (pin "K") (pinfunction "K_K") (pintype "passive"))
      (node (ref "R62") (pin "1") (pinfunction "1_1") (pintype "passive"))
    )
    (net (code "41") (name "Net-(D63-PadK)") (class "Default")
      (node (ref "D63") (pin "K") (pinfunction "K_K") (pintype "passive"))
      (node (ref "R63") (pin "1") (pinfunction "1_1") (pintype "passive"))
    )
    (net (code "42") (name "Net-(D64-PadK)") (class "Default")
      (node (ref "D64") (pin "K") (pinfunction "K_K") (pintype "passive"))
      (node (ref "R64") (pin "1") (pinfunction "1_1") (pintype "passive"))
    )
    (net (code "43") (name "Net-(D65-PadK)") (class "Default")
      (node (ref "D65") (pin "K") (pinfunction "K_K") (pintype "passive"))
      (node (ref "R65") (pin "1") (pinfunction "1_1") (pintype "passive"))
    )
    (net (code "44") (name "Net-(D66-PadK)") (class "Default")
      (node (ref "D66") (pin "K") (pinfunction "K_K") (pintype "passive"))
      (node (ref "R66") (pin "1") (pinfunction "1_1") (pintype "passive"))
    )
    (net (code "45") (name "Net-(D67-PadK)") (class "Default")
      (node (ref "D67") (pin "K") (pinfunction "K_K") (pintype "passive"))
      (node (ref "R67") (pin "1") (pinfunction "1_1") (pintype "passive"))
    )
    (net (code "46") (name "Net-(D68-PadK)") (class "Default")
      (node (ref "D68") (pin "K") (pinfunction "K_K") (pintype "passive"))
      (node (ref "R68") (pin "1") (pinfunction "1_1") (pintype "passive"))
    )
    (net (code "47") (name "Net-(D69-PadK)") (class "Default")
      (node (ref "D69") (pin "K") (pinfunction "K_K") (pintype "passive"))
      (node (ref "R69") (pin "1") (pinfunction "1_1") (pintype "passive"))
    )
    (net (code "48") (name "Net-(D70-PadK)") (class "Default")
      (node (ref "D70") (pin "K") (pinfunction "K_K") (pintype "passive"))
      (node (ref "R70") (pin "1") (pinfunction "1_1") (pintype "passive"))
    )
    (net (code "49") (name "Net-(D71-PadK)") (class "Default")
      (node (ref "D71") (pin "K") (pinfunction "K_K") (pintype "passive"))
      (node (ref "R71") (pin "1") (pinfunction "1_1") (pintype "passive"))
    )
    (net (code "50") (name "Net-(D72-PadK)") (class "Default")
      (node (ref "D72") (pin "K") (pinfunction "K_K") (pintype "passive"))
      (node (ref "R72") (pin "1") (pinfunction "1_1") (pintype "passive"))
    )
    (net (code "51") (name "Net-(D73-PadK)") (class "Default")
      (node (ref "D73") (pin "K") (pinfunction "K_K") (pintype "passive"))
      (node (ref "R73") (pin "1") (pinfunction "1_1") (pintype "passive"))
    )
    (net (code "52") (name "Net-(D74-PadK)") (class "Default")
      (node (ref "D74") (pin "K") (pinfunction "K_K") (pintype "passive"))
      (node (ref "R74") (pin "1") (pinfunction "1_1") (pintype "passive"))
    )
    (net (code "53") (name "Net-(D75-PadK)") (class "Default")
      (node (ref "D75") (pin "K") (pinfunction "K_K") (pintype "passive"))
      (node (ref "R75") (pin "1") (pinfunction "1_1") (pintype "passive"))
    )
    (net (code "54") (name "Net-(D76-PadK)") (class "Default")
      (node (ref "D76") (pin "K") (pinfunction "K_K") (pintype "passive"))
      (node (ref "R76") (pin "1") (pinfunction "1_1") (pintype "passive"))
    )
    (net (code "55") (name "Net-(D77-PadK)") (class "Default")
      (node (ref "D77") (pin "K") (pinfunction "K_K") (pintype "passive"))
      (node (ref "R77") (pin "1") (pinfunction "1_1") (pintype "passive"))
    )
    (net (code "56") (name "Net-(D78-PadK)") (class "Default")
      (node (ref "D78") (pin "K") (pinfunction "K_K") (pintype "passive"))
      (node (ref "R78") (pin "1") (pinfunction "1_1") (pintype "passive"))
    )
    (net (code "57") (name "Net-(D79-PadK)") (class "Default")
      (node (ref "D79") (pin "K") (pinfunction "K_K") (pintype "passive"))
      (node (ref "R79") (pin "1") (pinfunction "1_1") (pintype "passive"))
    )
    (net (code "58") (name "Net-(D80-PadK)") (class "Default")
      (node (ref "D80") (pin "K") (pinfunction "K_K") (pintype "passive"))
      (node (ref "R80") (pin "1") (pinfunction "1_1") (pintype "passive"))
    )
    (net (code "59") (name "unconnected-(USB1-CC1-PadA5)") (class "Default")
      (node (ref "USB1") (pin "A5") (pinfunction "CC1_A5") (pintype "passive"))
    )
    (net (code "60") (name "unconnected-(USB1-CC2-PadB5)") (class "Default")
      (node (ref "USB1") (pin "B5") (pinfunction "CC2_B5") (pintype "passive"))
    )
    (net (code "61") (name "unconnected-(USB1-GND-PadA12)") (class "Default")
      (node (ref "USB1") (pin "A12") (pinfunction "GND_A12") (pintype "passive"))
    )
    (net (code "62") (name "unconnected-(USB1-VBUS-PadA9)") (class "Default")
      (node (ref "USB1") (pin "A9") (pinfunction "VBUS_A9") (pintype "passive"))
    )
  )
)
